# CONTROL.net
KiCad netlist of a schematic drawn in Altium Designer
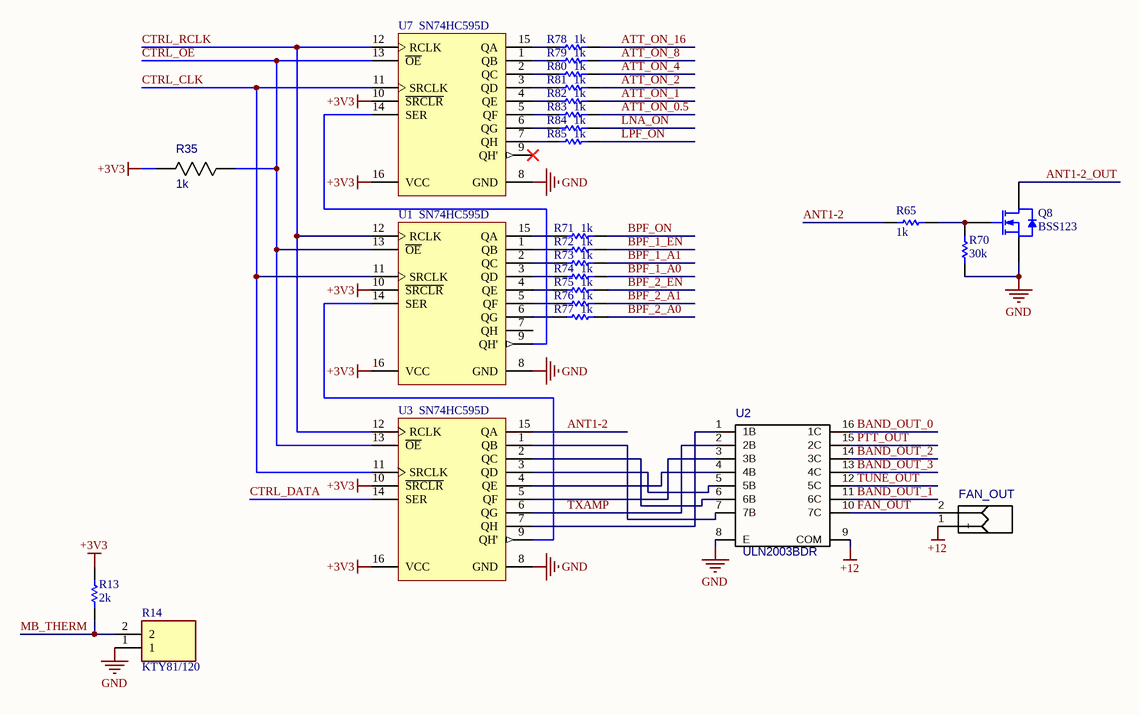
[diagram p0: CONTROL.SchDoc]

(export (version "E")
  (design (tool "Eeschema 10.0.6"))
  (components
    (comp (ref "FAN_OUT")
      (value "51022-0200")
      (footprint "51022-0200")
      (libsource (lib "*") (part "51022-0200"))
    )
    (comp (ref "Q8")
      (value "BSS123")
      (footprint "FAIR-SOT23-3_V")
      (fields (field (name "MANUFACTURER") "Fairchild"))
      (libsource (lib "Altium Content Vault") (part "NEMOS-GSD-3"))
    )
    (comp (ref "R13")
      (value "2k")
      (footprint "RESC2013X60X40NL20T25")
      (description "RES_0805")
      (fields (field (name "MANUFACTURER") "Panasonic") (field (name "PART NUMBER") "ERA-6AEB303V"))
      (libsource (lib "Altium Content Vault") (part "RES"))
    )
    (comp (ref "R14")
      (value "KTY81/120")
      (footprint "SamacSys:TO254P420X460X770-2P")
      (description "Integrated Circuit")
      (fields (field (name "MANUFACTURER_PART_NUMBER") "KTY81/110"))
      (libsource (lib "*") (part "KTY81_110"))
    )
    (comp (ref "R35")
      (value "1k")
      (footprint "RES_0805")
      (description "RES_0805")
      (libsource (lib "*") (part "RES_0805"))
    )
    (comp (ref "R65")
      (value "1k")
      (footprint "RESC2013X60X40NL20T25")
      (description "RES_0805")
      (fields (field (name "MANUFACTURER") "Panasonic") (field (name "PART NUMBER") "ERA-6AEB303V"))
      (libsource (lib "Altium Content Vault") (part "RES"))
    )
    (comp (ref "R70")
      (value "30k")
      (footprint "RESC2013X60X40NL20T25")
      (description "RES_0805")
      (fields (field (name "MANUFACTURER") "Panasonic") (field (name "PART NUMBER") "ERA-6AEB303V"))
      (libsource (lib "Altium Content Vault") (part "RES"))
    )
    (comp (ref "R71")
      (value "1k")
      (footprint "RESC2013X60X40NL20T25")
      (description "RES_0805")
      (fields (field (name "MANUFACTURER") "Panasonic") (field (name "PART NUMBER") "ERA-6AEB303V"))
      (libsource (lib "Altium Content Vault") (part "RES"))
    )
    (comp (ref "R72")
      (value "1k")
      (footprint "RESC2013X60X40NL20T25")
      (description "RES_0805")
      (fields (field (name "MANUFACTURER") "Panasonic") (field (name "PART NUMBER") "ERA-6AEB303V"))
      (libsource (lib "Altium Content Vault") (part "RES"))
    )
    (comp (ref "R73")
      (value "1k")
      (footprint "RESC2013X60X40NL20T25")
      (description "RES_0805")
      (fields (field (name "MANUFACTURER") "Panasonic") (field (name "PART NUMBER") "ERA-6AEB303V"))
      (libsource (lib "Altium Content Vault") (part "RES"))
    )
    (comp (ref "R74")
      (value "1k")
      (footprint "RESC2013X60X40NL20T25")
      (description "RES_0805")
      (fields (field (name "MANUFACTURER") "Panasonic") (field (name "PART NUMBER") "ERA-6AEB303V"))
      (libsource (lib "Altium Content Vault") (part "RES"))
    )
    (comp (ref "R75")
      (value "1k")
      (footprint "RESC2013X60X40NL20T25")
      (description "RES_0805")
      (fields (field (name "MANUFACTURER") "Panasonic") (field (name "PART NUMBER") "ERA-6AEB303V"))
      (libsource (lib "Altium Content Vault") (part "RES"))
    )
    (comp (ref "R76")
      (value "1k")
      (footprint "RESC2013X60X40NL20T25")
      (description "RES_0805")
      (fields (field (name "MANUFACTURER") "Panasonic") (field (name "PART NUMBER") "ERA-6AEB303V"))
      (libsource (lib "Altium Content Vault") (part "RES"))
    )
    (comp (ref "R77")
      (value "1k")
      (footprint "RESC2013X60X40NL20T25")
      (description "RES_0805")
      (fields (field (name "MANUFACTURER") "Panasonic") (field (name "PART NUMBER") "ERA-6AEB303V"))
      (libsource (lib "Altium Content Vault") (part "RES"))
    )
    (comp (ref "R78")
      (value "1k")
      (footprint "RESC2013X60X40NL20T25")
      (description "RES_0805")
      (fields (field (name "MANUFACTURER") "Panasonic") (field (name "PART NUMBER") "ERA-6AEB303V"))
      (libsource (lib "Altium Content Vault") (part "RES"))
    )
    (comp (ref "R79")
      (value "1k")
      (footprint "RESC2013X60X40NL20T25")
      (description "RES_0805")
      (fields (field (name "MANUFACTURER") "Panasonic") (field (name "PART NUMBER") "ERA-6AEB303V"))
      (libsource (lib "Altium Content Vault") (part "RES"))
    )
    (comp (ref "R80")
      (value "1k")
      (footprint "RESC2013X60X40NL20T25")
      (description "RES_0805")
      (fields (field (name "MANUFACTURER") "Panasonic") (field (name "PART NUMBER") "ERA-6AEB303V"))
      (libsource (lib "Altium Content Vault") (part "RES"))
    )
    (comp (ref "R81")
      (value "1k")
      (footprint "RESC2013X60X40NL20T25")
      (description "RES_0805")
      (fields (field (name "MANUFACTURER") "Panasonic") (field (name "PART NUMBER") "ERA-6AEB303V"))
      (libsource (lib "Altium Content Vault") (part "RES"))
    )
    (comp (ref "R82")
      (value "1k")
      (footprint "RESC2013X60X40NL20T25")
      (description "RES_0805")
      (fields (field (name "MANUFACTURER") "Panasonic") (field (name "PART NUMBER") "ERA-6AEB303V"))
      (libsource (lib "Altium Content Vault") (part "RES"))
    )
    (comp (ref "R83")
      (value "1k")
      (footprint "RESC2013X60X40NL20T25")
      (description "RES_0805")
      (fields (field (name "MANUFACTURER") "Panasonic") (field (name "PART NUMBER") "ERA-6AEB303V"))
      (libsource (lib "Altium Content Vault") (part "RES"))
    )
    (comp (ref "R84")
      (value "1k")
      (footprint "RESC2013X60X40NL20T25")
      (description "RES_0805")
      (fields (field (name "MANUFACTURER") "Panasonic") (field (name "PART NUMBER") "ERA-6AEB303V"))
      (libsource (lib "Altium Content Vault") (part "RES"))
    )
    (comp (ref "R85")
      (value "1k")
      (footprint "RESC2013X60X40NL20T25")
      (description "RES_0805")
      (fields (field (name "MANUFACTURER") "Panasonic") (field (name "PART NUMBER") "ERA-6AEB303V"))
      (libsource (lib "Altium Content Vault") (part "RES"))
    )
    (comp (ref "U1")
      (value "SN74HC595D")
      (footprint "D0016A_L")
      (description "8-Bit Shift Registers With 3-State Output Registers, D0016A, TUBE")
      (fields
        (field (name "GENERIC PART NUMBER") "SN74HC595")
        (field (name "MANUFACTURER") "Texas Instruments")
      )
      (libsource (lib "Altium Content Vault") (part "TI-SN74XHCT595X_SN74LV595A-16"))
    )
    (comp (ref "U2")
      (value "ULN2003BDR")
      (footprint "ULN2003BDR")
      (libsource (lib "RF-UNIT") (part "ULN2003BDR"))
    )
    (comp (ref "U3")
      (value "SN74HC595D")
      (footprint "D0016A_L")
      (description "8-Bit Shift Registers With 3-State Output Registers, D0016A, TUBE")
      (fields
        (field (name "GENERIC PART NUMBER") "SN74HC595")
        (field (name "MANUFACTURER") "Texas Instruments")
      )
      (libsource (lib "Altium Content Vault") (part "TI-SN74XHCT595X_SN74LV595A-16"))
    )
    (comp (ref "U7")
      (value "SN74HC595D")
      (footprint "D0016A_L")
      (description "8-Bit Shift Registers With 3-State Output Registers, D0016A, TUBE")
      (fields
        (field (name "GENERIC PART NUMBER") "SN74HC595")
        (field (name "MANUFACTURER") "Texas Instruments")
      )
      (libsource (lib "Altium Content Vault") (part "TI-SN74XHCT595X_SN74LV595A-16"))
    )
  )
  (nets
    (net (code "1") (name "+3V3") (class "Default")
      (node (ref "R13") (pin "1") (pinfunction "1_1") (pintype "passive"))
      (node (ref "R35") (pin "1") (pinfunction "1_1") (pintype "passive"))
      (node (ref "U1") (pin "10") (pinfunction "~{SRCLR}_10") (pintype "passive"))
      (node (ref "U1") (pin "16") (pinfunction "VCC_16") (pintype "power_in"))
      (node (ref "U3") (pin "10") (pinfunction "~{SRCLR}_10") (pintype "passive"))
      (node (ref "U3") (pin "16") (pinfunction "VCC_16") (pintype "power_in"))
      (node (ref "U7") (pin "10") (pinfunction "~{SRCLR}_10") (pintype "passive"))
      (node (ref "U7") (pin "16") (pinfunction "VCC_16") (pintype "power_in"))
    )
    (net (code "2") (name "+12") (class "Default")
      (node (ref "FAN_OUT") (pin "1") (pinfunction "+_1") (pintype "passive"))
      (node (ref "U2") (pin "9") (pinfunction "COM_9") (pintype "passive"))
    )
    (net (code "4") (name "/ANT1-2") (class "Default")
      (node (ref "R65") (pin "2") (pinfunction "2_2") (pintype "passive"))
      (node (ref "U3") (pin "15") (pinfunction "QA_15") (pintype "tri_state"))
    )
    (net (code "5") (name "/ANT1-2_OUT") (class "Default")
      (node (ref "Q8") (pin "3") (pinfunction "D_3") (pintype "passive"))
    )
    (net (code "6") (name "/ATT_ON_0.5") (class "Default")
      (node (ref "R83") (pin "1") (pinfunction "1_1") (pintype "passive"))
    )
    (net (code "7") (name "/ATT_ON_1") (class "Default")
      (node (ref "R82") (pin "1") (pinfunction "1_1") (pintype "passive"))
    )
    (net (code "8") (name "/ATT_ON_2") (class "Default")
      (node (ref "R81") (pin "1") (pinfunction "1_1") (pintype "passive"))
    )
    (net (code "9") (name "/ATT_ON_4") (class "Default")
      (node (ref "R80") (pin "1") (pinfunction "1_1") (pintype "passive"))
    )
    (net (code "10") (name "/ATT_ON_8") (class "Default")
      (node (ref "R79") (pin "1") (pinfunction "1_1") (pintype "passive"))
    )
    (net (code "11") (name "/ATT_ON_16") (class "Default")
      (node (ref "R78") (pin "1") (pinfunction "1_1") (pintype "passive"))
    )
    (net (code "12") (name "/BAND_OUT_0") (class "Default")
      (node (ref "U2") (pin "16") (pinfunction "1C_16") (pintype "passive"))
    )
    (net (code "13") (name "/BAND_OUT_1") (class "Default")
      (node (ref "U2") (pin "11") (pinfunction "6C_11") (pintype "passive"))
    )
    (net (code "14") (name "/BAND_OUT_2") (class "Default")
      (node (ref "U2") (pin "14") (pinfunction "3C_14") (pintype "passive"))
    )
    (net (code "15") (name "/BAND_OUT_3") (class "Default")
      (node (ref "U2") (pin "13") (pinfunction "4C_13") (pintype "passive"))
    )
    (net (code "16") (name "/BPF_1_A0") (class "Default")
      (node (ref "R74") (pin "1") (pinfunction "1_1") (pintype "passive"))
    )
    (net (code "17") (name "/BPF_1_A1") (class "Default")
      (node (ref "R73") (pin "1") (pinfunction "1_1") (pintype "passive"))
    )
    (net (code "18") (name "/BPF_1_EN") (class "Default")
      (node (ref "R72") (pin "1") (pinfunction "1_1") (pintype "passive"))
    )
    (net (code "19") (name "/BPF_2_A0") (class "Default")
      (node (ref "R77") (pin "1") (pinfunction "1_1") (pintype "passive"))
    )
    (net (code "20") (name "/BPF_2_A1") (class "Default")
      (node (ref "R76") (pin "1") (pinfunction "1_1") (pintype "passive"))
    )
    (net (code "21") (name "/BPF_2_EN") (class "Default")
      (node (ref "R75") (pin "1") (pinfunction "1_1") (pintype "passive"))
    )
    (net (code "22") (name "/BPF_ON") (class "Default")
      (node (ref "R71") (pin "1") (pinfunction "1_1") (pintype "passive"))
    )
    (net (code "23") (name "/CTRL_CLK") (class "Default")
      (node (ref "U1") (pin "11") (pinfunction "SRCLK_11") (pintype "passive"))
      (node (ref "U3") (pin "11") (pinfunction "SRCLK_11") (pintype "passive"))
      (node (ref "U7") (pin "11") (pinfunction "SRCLK_11") (pintype "passive"))
    )
    (net (code "24") (name "/CTRL_DATA") (class "Default")
      (node (ref "U3") (pin "14") (pinfunction "SER_14") (pintype "passive"))
    )
    (net (code "25") (name "/CTRL_OE") (class "Default")
      (node (ref "R35") (pin "2") (pinfunction "2_2") (pintype "passive"))
      (node (ref "U1") (pin "13") (pinfunction "~{OE}_13") (pintype "passive"))
      (node (ref "U3") (pin "13") (pinfunction "~{OE}_13") (pintype "passive"))
      (node (ref "U7") (pin "13") (pinfunction "~{OE}_13") (pintype "passive"))
    )
    (net (code "26") (name "/CTRL_RCLK") (class "Default")
      (node (ref "U1") (pin "12") (pinfunction "RCLK_12") (pintype "passive"))
      (node (ref "U3") (pin "12") (pinfunction "RCLK_12") (pintype "passive"))
      (node (ref "U7") (pin "12") (pinfunction "RCLK_12") (pintype "passive"))
    )
    (net (code "27") (name "/FAN_OUT") (class "Default")
      (node (ref "FAN_OUT") (pin "2") (pinfunction "-_2") (pintype "passive"))
      (node (ref "U2") (pin "10") (pinfunction "7C_10") (pintype "passive"))
    )
    (net (code "28") (name "/LNA_ON") (class "Default")
      (node (ref "R84") (pin "1") (pinfunction "1_1") (pintype "passive"))
    )
    (net (code "29") (name "/LPF_ON") (class "Default")
      (node (ref "R85") (pin "1") (pinfunction "1_1") (pintype "passive"))
    )
    (net (code "30") (name "/MB_THERM") (class "Default")
      (node (ref "R13") (pin "2") (pinfunction "2_2") (pintype "passive"))
      (node (ref "R14") (pin "2") (pinfunction "2_2") (pintype "passive"))
    )
    (net (code "31") (name "/PTT_OUT") (class "Default")
      (node (ref "U2") (pin "15") (pinfunction "2C_15") (pintype "passive"))
    )
    (net (code "32") (name "/TUNE_OUT") (class "Default")
      (node (ref "U2") (pin "12") (pinfunction "5C_12") (pintype "passive"))
    )
    (net (code "33") (name "/TXAMP") (class "Default")
      (node (ref "U2") (pin "2") (pinfunction "2B_2") (pintype "passive"))
      (node (ref "U3") (pin "6") (pinfunction "QG_6") (pintype "tri_state"))
    )
    (net (code "34") (name "GND") (class "Default")
      (node (ref "Q8") (pin "2") (pinfunction "S_2") (pintype "passive"))
      (node (ref "R14") (pin "1") (pinfunction "1_1") (pintype "passive"))
      (node (ref "R70") (pin "1") (pinfunction "1_1") (pintype "passive"))
      (node (ref "U1") (pin "8") (pinfunction "GND_8") (pintype "power_in"))
      (node (ref "U2") (pin "8") (pinfunction "E_8") (pintype "passive"))
      (node (ref "U3") (pin "8") (pinfunction "GND_8") (pintype "power_in"))
      (node (ref "U7") (pin "8") (pinfunction "GND_8") (pintype "power_in"))
    )
    (net (code "35") (name "Net-(Q8-G)") (class "Default")
      (node (ref "Q8") (pin "1") (pinfunction "G_1") (pintype "passive"))
      (node (ref "R65") (pin "1") (pinfunction "1_1") (pintype "passive"))
      (node (ref "R70") (pin "2") (pinfunction "2_2") (pintype "passive"))
    )
    (net (code "36") (name "Net-(U1-QA)") (class "Default")
      (node (ref "R71") (pin "2") (pinfunction "2_2") (pintype "passive"))
      (node (ref "U1") (pin "15") (pinfunction "QA_15") (pintype "tri_state"))
    )
    (net (code "37") (name "Net-(U1-QB)") (class "Default")
      (node (ref "R72") (pin "2") (pinfunction "2_2") (pintype "passive"))
      (node (ref "U1") (pin "1") (pinfunction "QB_1") (pintype "tri_state"))
    )
    (net (code "38") (name "Net-(U1-QC)") (class "Default")
      (node (ref "R73") (pin "2") (pinfunction "2_2") (pintype "passive"))
      (node (ref "U1") (pin "2") (pinfunction "QC_2") (pintype "tri_state"))
    )
    (net (code "39") (name "Net-(U1-QD)") (class "Default")
      (node (ref "R74") (pin "2") (pinfunction "2_2") (pintype "passive"))
      (node (ref "U1") (pin "3") (pinfunction "QD_3") (pintype "tri_state"))
    )
    (net (code "40") (name "Net-(U1-QE)") (class "Default")
      (node (ref "R75") (pin "2") (pinfunction "2_2") (pintype "passive"))
      (node (ref "U1") (pin "4") (pinfunction "QE_4") (pintype "tri_state"))
    )
    (net (code "41") (name "Net-(U1-QF)") (class "Default")
      (node (ref "R76") (pin "2") (pinfunction "2_2") (pintype "passive"))
      (node (ref "U1") (pin "5") (pinfunction "QF_5") (pintype "tri_state"))
    )
    (net (code "42") (name "Net-(U1-QG)") (class "Default")
      (node (ref "R77") (pin "2") (pinfunction "2_2") (pintype "passive"))
      (node (ref "U1") (pin "6") (pinfunction "QG_6") (pintype "tri_state"))
    )
    (net (code "43") (name "Net-(U1-QH')") (class "Default")
      (node (ref "U1") (pin "9") (pinfunction "QH'_9") (pintype "output"))
      (node (ref "U7") (pin "14") (pinfunction "SER_14") (pintype "passive"))
    )
    (net (code "44") (name "Net-(U1-SER)") (class "Default")
      (node (ref "U1") (pin "14") (pinfunction "SER_14") (pintype "passive"))
      (node (ref "U3") (pin "9") (pinfunction "QH'_9") (pintype "output"))
    )
    (net (code "45") (name "Net-(U2-1B)") (class "Default")
      (node (ref "U2") (pin "1") (pinfunction "1B_1") (pintype "passive"))
      (node (ref "U3") (pin "7") (pinfunction "QH_7") (pintype "tri_state"))
    )
    (net (code "46") (name "Net-(U2-3B)") (class "Default")
      (node (ref "U2") (pin "3") (pinfunction "3B_3") (pintype "passive"))
      (node (ref "U3") (pin "5") (pinfunction "QF_5") (pintype "tri_state"))
    )
    (net (code "47") (name "Net-(U2-4B)") (class "Default")
      (node (ref "U2") (pin "4") (pinfunction "4B_4") (pintype "passive"))
      (node (ref "U3") (pin "4") (pinfunction "QE_4") (pintype "tri_state"))
    )
    (net (code "48") (name "Net-(U2-5B)") (class "Default")
      (node (ref "U2") (pin "5") (pinfunction "5B_5") (pintype "passive"))
      (node (ref "U3") (pin "3") (pinfunction "QD_3") (pintype "tri_state"))
    )
    (net (code "49") (name "Net-(U2-6B)") (class "Default")
      (node (ref "U2") (pin "6") (pinfunction "6B_6") (pintype "passive"))
      (node (ref "U3") (pin "2") (pinfunction "QC_2") (pintype "tri_state"))
    )
    (net (code "50") (name "Net-(U2-7B)") (class "Default")
      (node (ref "U2") (pin "7") (pinfunction "7B_7") (pintype "passive"))
      (node (ref "U3") (pin "1") (pinfunction "QB_1") (pintype "tri_state"))
    )
    (net (code "51") (name "Net-(U7-QA)") (class "Default")
      (node (ref "R78") (pin "2") (pinfunction "2_2") (pintype "passive"))
      (node (ref "U7") (pin "15") (pinfunction "QA_15") (pintype "tri_state"))
    )
    (net (code "52") (name "Net-(U7-QB)") (class "Default")
      (node (ref "R79") (pin "2") (pinfunction "2_2") (pintype "passive"))
      (node (ref "U7") (pin "1") (pinfunction "QB_1") (pintype "tri_state"))
    )
    (net (code "53") (name "Net-(U7-QC)") (class "Default")
      (node (ref "R80") (pin "2") (pinfunction "2_2") (pintype "passive"))
      (node (ref "U7") (pin "2") (pinfunction "QC_2") (pintype "tri_state"))
    )
    (net (code "54") (name "Net-(U7-QD)") (class "Default")
      (node (ref "R81") (pin "2") (pinfunction "2_2") (pintype "passive"))
      (node (ref "U7") (pin "3") (pinfunction "QD_3") (pintype "tri_state"))
    )
    (net (code "55") (name "Net-(U7-QE)") (class "Default")
      (node (ref "R82") (pin "2") (pinfunction "2_2") (pintype "passive"))
      (node (ref "U7") (pin "4") (pinfunction "QE_4") (pintype "tri_state"))
    )
    (net (code "56") (name "Net-(U7-QF)") (class "Default")
      (node (ref "R83") (pin "2") (pinfunction "2_2") (pintype "passive"))
      (node (ref "U7") (pin "5") (pinfunction "QF_5") (pintype "tri_state"))
    )
    (net (code "57") (name "Net-(U7-QG)") (class "Default")
      (node (ref "R84") (pin "2") (pinfunction "2_2") (pintype "passive"))
      (node (ref "U7") (pin "6") (pinfunction "QG_6") (pintype "tri_state"))
    )
    (net (code "58") (name "Net-(U7-QH)") (class "Default")
      (node (ref "R85") (pin "2") (pinfunction "2_2") (pintype "passive"))
      (node (ref "U7") (pin "7") (pinfunction "QH_7") (pintype "tri_state"))
    )
    (net (code "59") (name "unconnected-(U1-QH-Pad7)") (class "Default")
      (node (ref "U1") (pin "7") (pinfunction "QH_7") (pintype "tri_state"))
    )
    (net (code "60") (name "unconnected-(U7-QH'-Pad9)") (class "Default")
      (node (ref "U7") (pin "9") (pinfunction "QH'_9") (pintype "output+no_connect"))
    )
  )
)
